# 601_PCIe-USB.net
KiCad netlist of a schematic drawn in Altium Designer
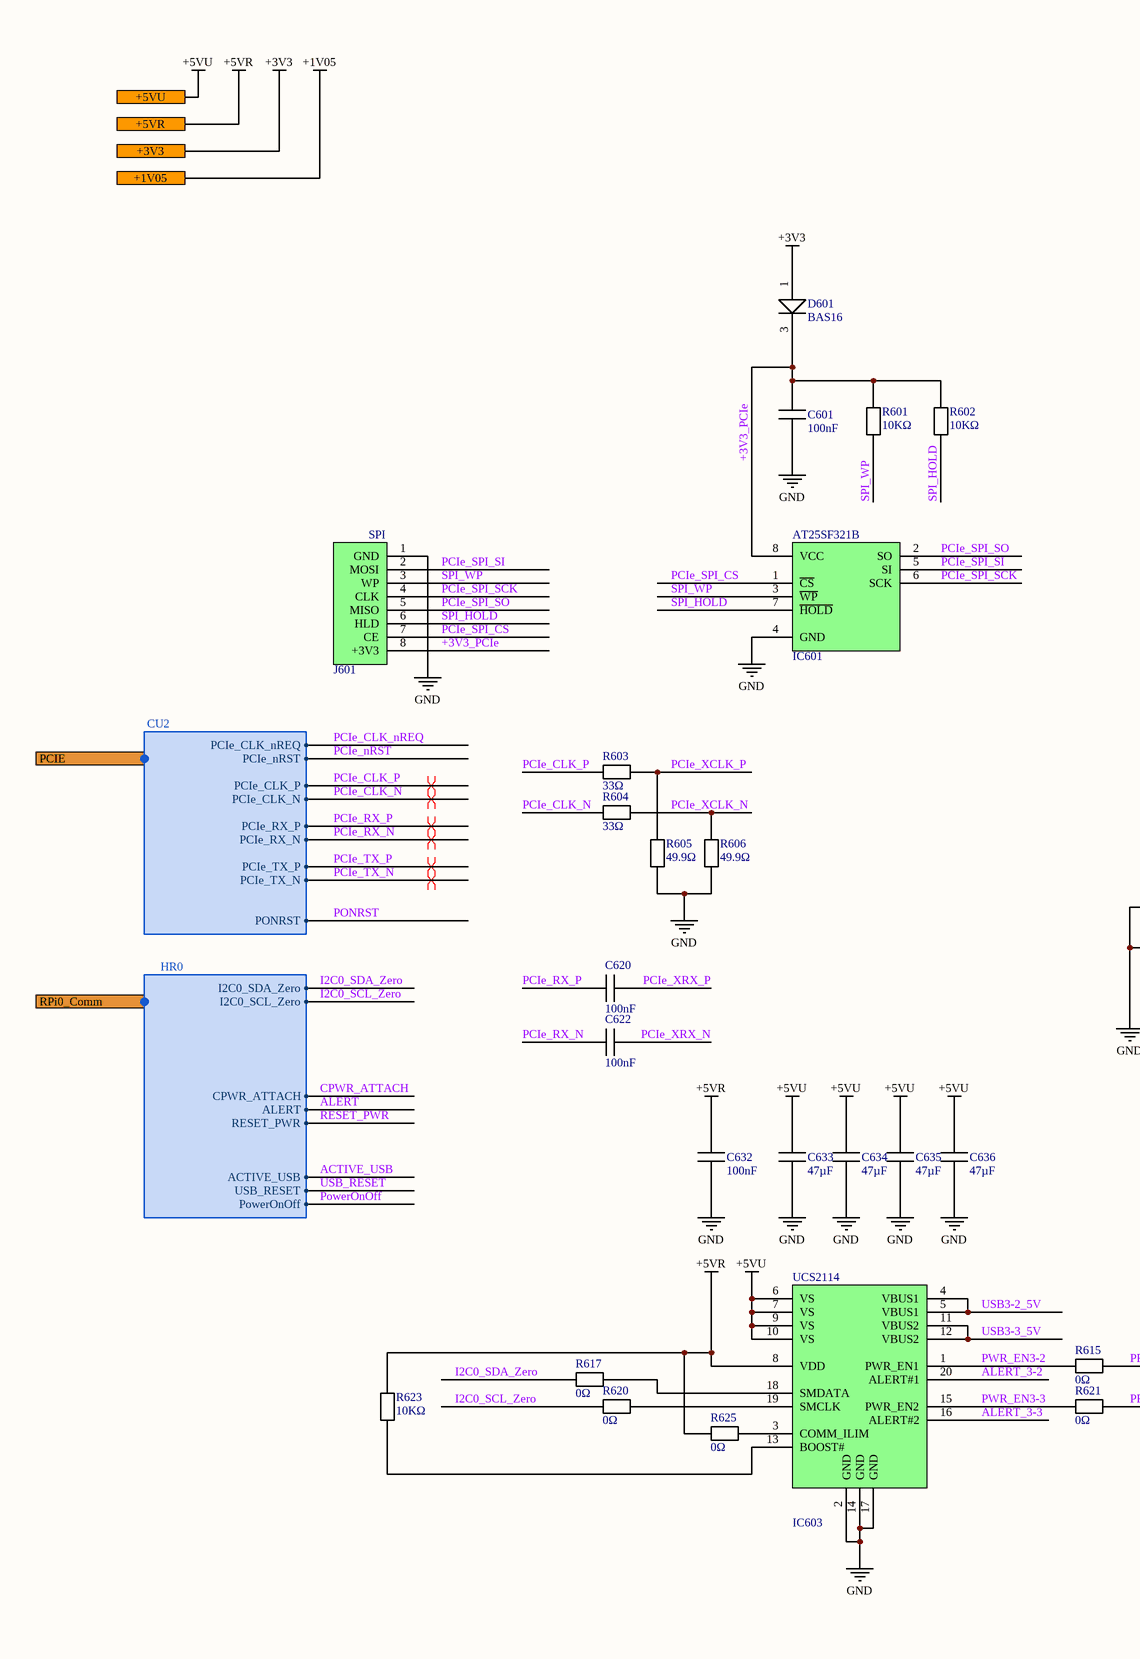
[diagram p0: 601_PCIe-USB.SchDoc, left]
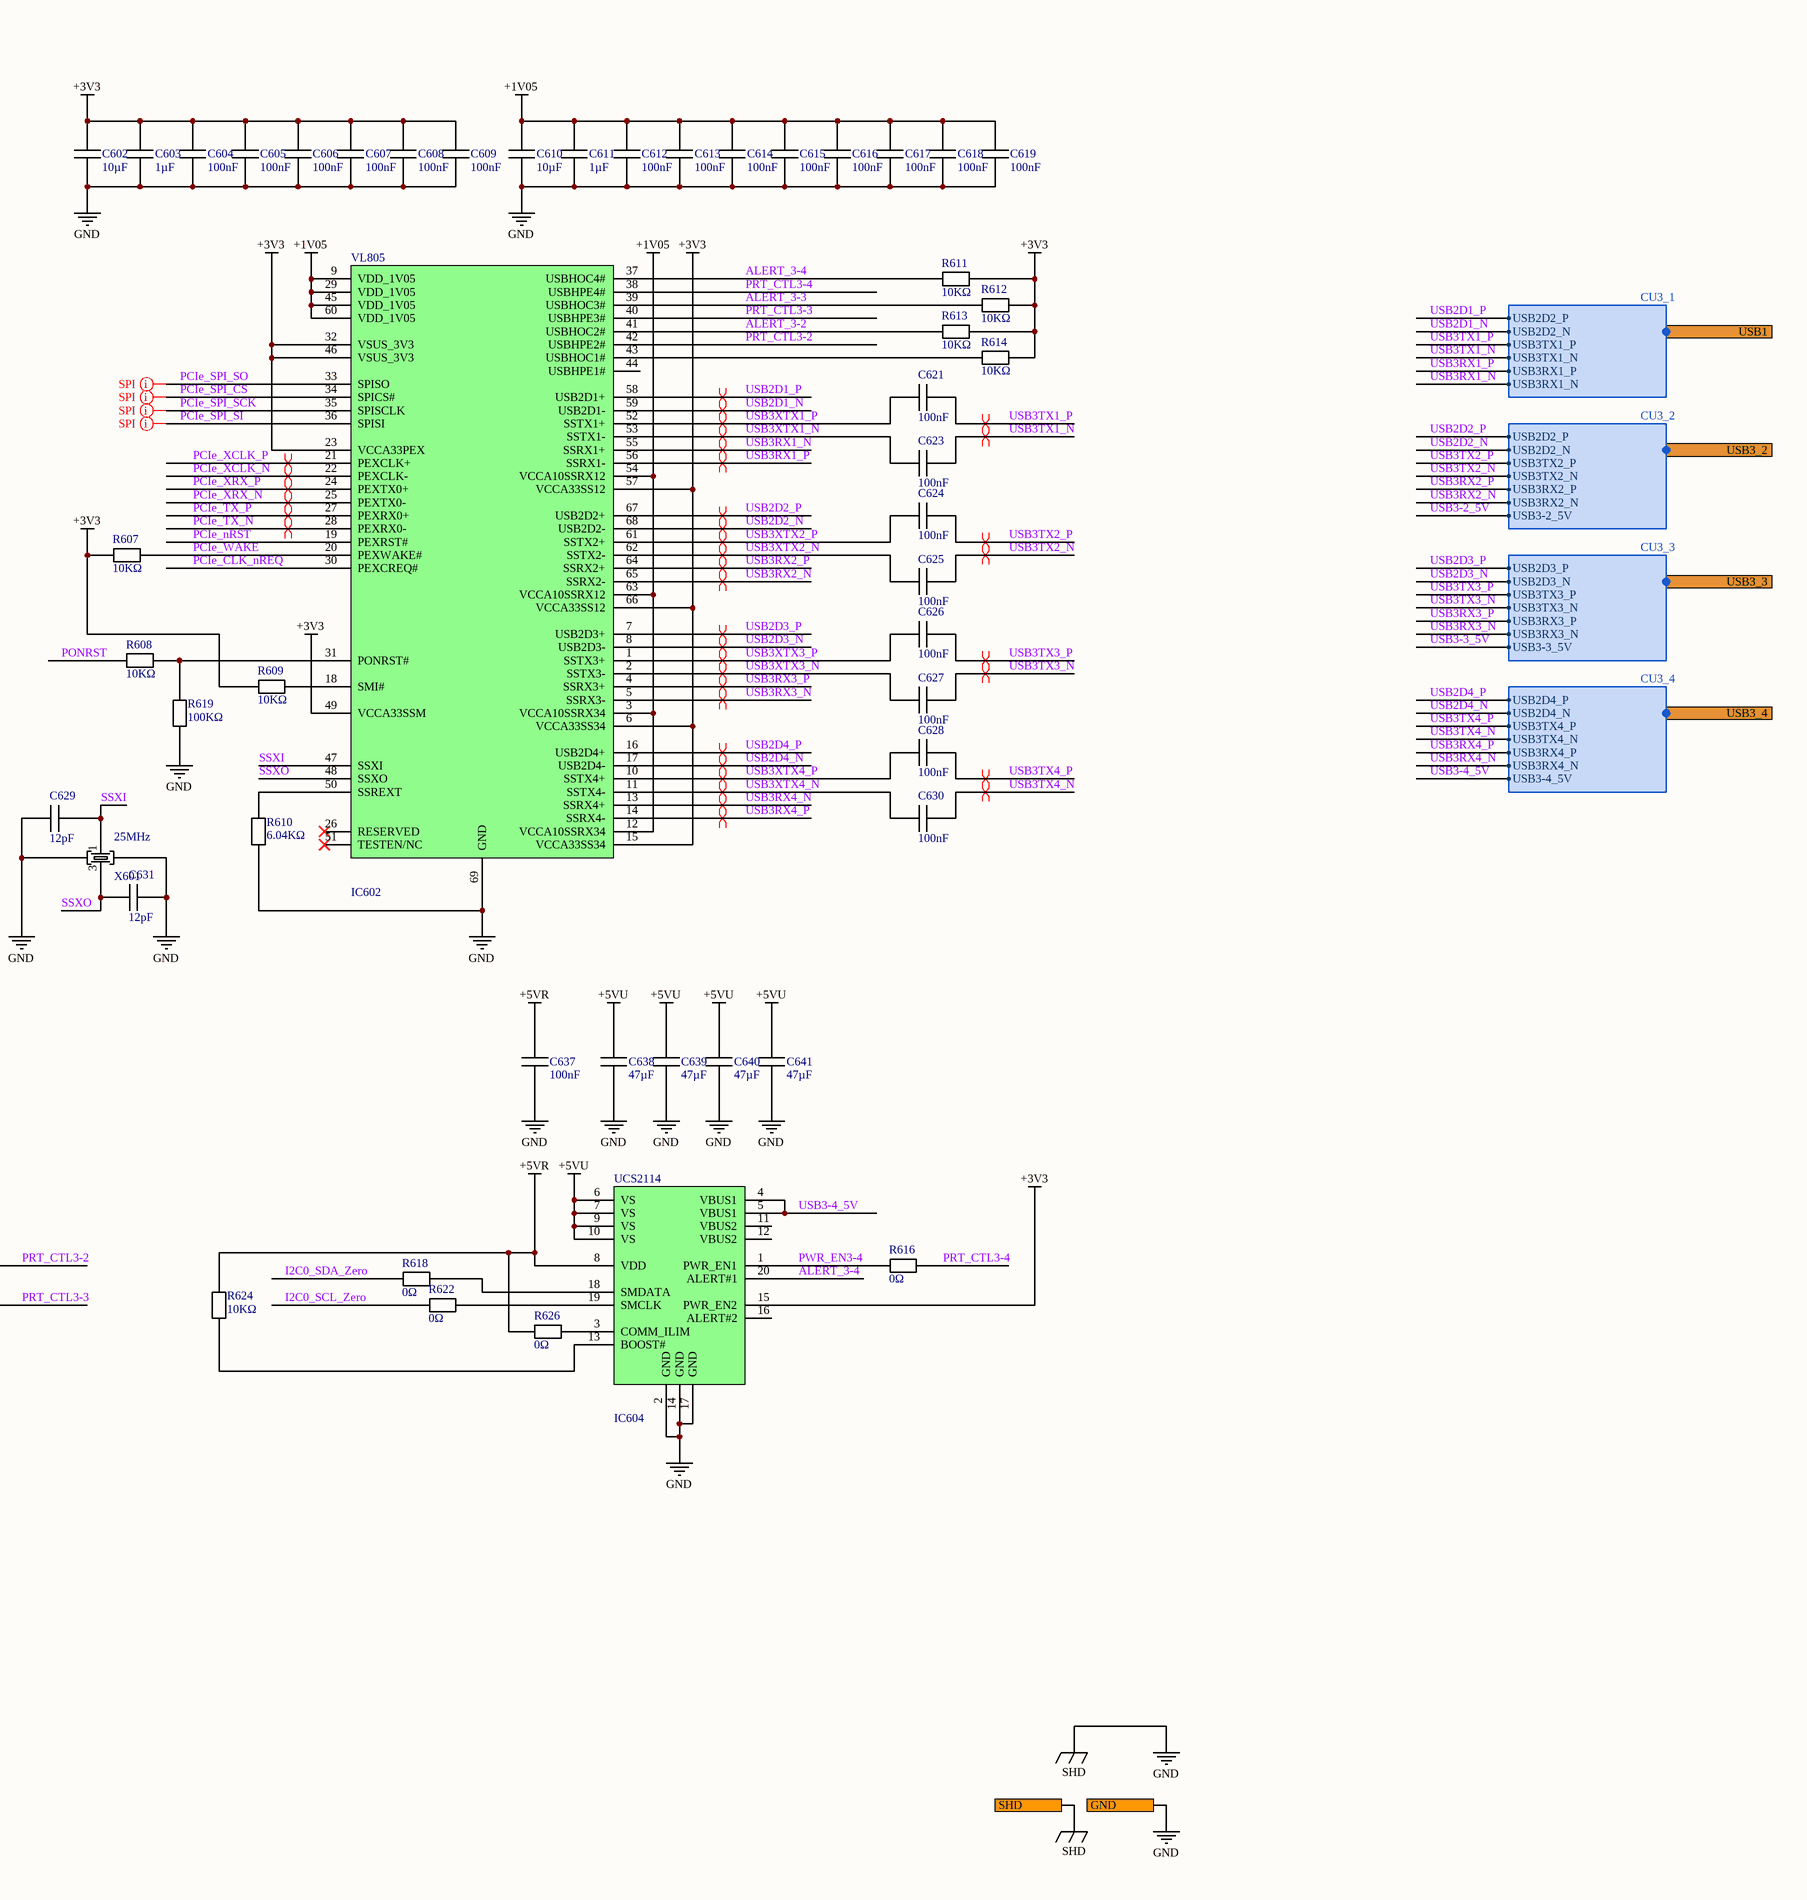
[diagram p1: 601_PCIe-USB.SchDoc, right]

(export (version "E")
  (design (tool "Eeschema 10.0.6"))
  (components
    (comp (ref "C601")
      (value "100nF")
      (footprint "C0402")
      (description "100nF 16V 10% X7R")
      (fields
        (field (name "REFVAL") "100nF")
        (field (name "PART NUMBER") "CA0010")
        (field (name "MANFACTPART") "GCM155R71C104KA55D")
      )
      (libsource (lib "GTS_Database") (part "C"))
    )
    (comp (ref "C602")
      (value "10µF")
      (footprint "C0603")
      (description "10µF 16V 20% X5R")
      (fields
        (field (name "REFVAL") "10µF")
        (field (name "PART NUMBER") "CA0008")
        (field (name "MANFACTPART") "GRM188R61C106MAALD")
      )
      (libsource (lib "GTS_Database") (part "C"))
    )
    (comp (ref "C603")
      (value "1µF")
      (footprint "C0603")
      (description "1µF 16V 10% X5R")
      (fields
        (field (name "REFVAL") "1µF")
        (field (name "PART NUMBER") "CA0003")
        (field (name "MANFACTPART") "C1608X5R1C105K080AA")
      )
      (libsource (lib "GTS_Database") (part "C"))
    )
    (comp (ref "C604")
      (value "100nF")
      (footprint "C0402")
      (description "100nF 16V 10% X7R")
      (fields
        (field (name "REFVAL") "100nF")
        (field (name "PART NUMBER") "CA0010")
        (field (name "MANFACTPART") "GCM155R71C104KA55D")
      )
      (libsource (lib "GTS_Database") (part "C"))
    )
    (comp (ref "C605")
      (value "100nF")
      (footprint "C0402")
      (description "100nF 16V 10% X7R")
      (fields
        (field (name "REFVAL") "100nF")
        (field (name "PART NUMBER") "CA0010")
        (field (name "MANFACTPART") "GCM155R71C104KA55D")
      )
      (libsource (lib "GTS_Database") (part "C"))
    )
    (comp (ref "C606")
      (value "100nF")
      (footprint "C0402")
      (description "100nF 16V 10% X7R")
      (fields
        (field (name "REFVAL") "100nF")
        (field (name "PART NUMBER") "CA0010")
        (field (name "MANFACTPART") "GCM155R71C104KA55D")
      )
      (libsource (lib "GTS_Database") (part "C"))
    )
    (comp (ref "C607")
      (value "100nF")
      (footprint "C0402")
      (description "100nF 16V 10% X7R")
      (fields
        (field (name "REFVAL") "100nF")
        (field (name "PART NUMBER") "CA0010")
        (field (name "MANFACTPART") "GCM155R71C104KA55D")
      )
      (libsource (lib "GTS_Database") (part "C"))
    )
    (comp (ref "C608")
      (value "100nF")
      (footprint "C0402")
      (description "100nF 16V 10% X7R")
      (fields
        (field (name "REFVAL") "100nF")
        (field (name "PART NUMBER") "CA0010")
        (field (name "MANFACTPART") "GCM155R71C104KA55D")
      )
      (libsource (lib "GTS_Database") (part "C"))
    )
    (comp (ref "C609")
      (value "100nF")
      (footprint "C0402")
      (description "100nF 16V 10% X7R")
      (fields
        (field (name "REFVAL") "100nF")
        (field (name "PART NUMBER") "CA0010")
        (field (name "MANFACTPART") "GCM155R71C104KA55D")
      )
      (libsource (lib "GTS_Database") (part "C"))
    )
    (comp (ref "C610")
      (value "10µF")
      (footprint "C0603")
      (description "10µF 16V 20% X5R")
      (fields
        (field (name "REFVAL") "10µF")
        (field (name "PART NUMBER") "CA0008")
        (field (name "MANFACTPART") "GRM188R61C106MAALD")
      )
      (libsource (lib "GTS_Database") (part "C"))
    )
    (comp (ref "C611")
      (value "1µF")
      (footprint "C0603")
      (description "1µF 16V 10% X5R")
      (fields
        (field (name "REFVAL") "1µF")
        (field (name "PART NUMBER") "CA0003")
        (field (name "MANFACTPART") "C1608X5R1C105K080AA")
      )
      (libsource (lib "GTS_Database") (part "C"))
    )
    (comp (ref "C612")
      (value "100nF")
      (footprint "C0402")
      (description "100nF 16V 10% X7R")
      (fields
        (field (name "REFVAL") "100nF")
        (field (name "PART NUMBER") "CA0010")
        (field (name "MANFACTPART") "GCM155R71C104KA55D")
      )
      (libsource (lib "GTS_Database") (part "C"))
    )
    (comp (ref "C613")
      (value "100nF")
      (footprint "C0402")
      (description "100nF 16V 10% X7R")
      (fields
        (field (name "REFVAL") "100nF")
        (field (name "PART NUMBER") "CA0010")
        (field (name "MANFACTPART") "GCM155R71C104KA55D")
      )
      (libsource (lib "GTS_Database") (part "C"))
    )
    (comp (ref "C614")
      (value "100nF")
      (footprint "C0402")
      (description "100nF 16V 10% X7R")
      (fields
        (field (name "REFVAL") "100nF")
        (field (name "PART NUMBER") "CA0010")
        (field (name "MANFACTPART") "GCM155R71C104KA55D")
      )
      (libsource (lib "GTS_Database") (part "C"))
    )
    (comp (ref "C615")
      (value "100nF")
      (footprint "C0402")
      (description "100nF 16V 10% X7R")
      (fields
        (field (name "REFVAL") "100nF")
        (field (name "PART NUMBER") "CA0010")
        (field (name "MANFACTPART") "GCM155R71C104KA55D")
      )
      (libsource (lib "GTS_Database") (part "C"))
    )
    (comp (ref "C616")
      (value "100nF")
      (footprint "C0402")
      (description "100nF 16V 10% X7R")
      (fields
        (field (name "REFVAL") "100nF")
        (field (name "PART NUMBER") "CA0010")
        (field (name "MANFACTPART") "GCM155R71C104KA55D")
      )
      (libsource (lib "GTS_Database") (part "C"))
    )
    (comp (ref "C617")
      (value "100nF")
      (footprint "C0402")
      (description "100nF 16V 10% X7R")
      (fields
        (field (name "REFVAL") "100nF")
        (field (name "PART NUMBER") "CA0010")
        (field (name "MANFACTPART") "GCM155R71C104KA55D")
      )
      (libsource (lib "GTS_Database") (part "C"))
    )
    (comp (ref "C618")
      (value "100nF")
      (footprint "C0402")
      (description "100nF 16V 10% X7R")
      (fields
        (field (name "REFVAL") "100nF")
        (field (name "PART NUMBER") "CA0010")
        (field (name "MANFACTPART") "GCM155R71C104KA55D")
      )
      (libsource (lib "GTS_Database") (part "C"))
    )
    (comp (ref "C619")
      (value "100nF")
      (footprint "C0402")
      (description "100nF 16V 10% X7R")
      (fields
        (field (name "REFVAL") "100nF")
        (field (name "PART NUMBER") "CA0010")
        (field (name "MANFACTPART") "GCM155R71C104KA55D")
      )
      (libsource (lib "GTS_Database") (part "C"))
    )
    (comp (ref "C620")
      (value "100nF")
      (footprint "C0402")
      (description "100nF 16V 10% X7R")
      (fields
        (field (name "REFVAL") "100nF")
        (field (name "PART NUMBER") "CA0010")
        (field (name "MANFACTPART") "GCM155R71C104KA55D")
      )
      (libsource (lib "GTS_Database") (part "C"))
    )
    (comp (ref "C621")
      (value "100nF")
      (footprint "C0402")
      (description "100nF 16V 10% X7R")
      (fields
        (field (name "REFVAL") "100nF")
        (field (name "PART NUMBER") "CA0010")
        (field (name "MANFACTPART") "GCM155R71C104KA55D")
      )
      (libsource (lib "GTS_Database") (part "C"))
    )
    (comp (ref "C622")
      (value "100nF")
      (footprint "C0402")
      (description "100nF 16V 10% X7R")
      (fields
        (field (name "REFVAL") "100nF")
        (field (name "PART NUMBER") "CA0010")
        (field (name "MANFACTPART") "GCM155R71C104KA55D")
      )
      (libsource (lib "GTS_Database") (part "C"))
    )
    (comp (ref "C623")
      (value "100nF")
      (footprint "C0402")
      (description "100nF 16V 10% X7R")
      (fields
        (field (name "REFVAL") "100nF")
        (field (name "PART NUMBER") "CA0010")
        (field (name "MANFACTPART") "GCM155R71C104KA55D")
      )
      (libsource (lib "GTS_Database") (part "C"))
    )
    (comp (ref "C624")
      (value "100nF")
      (footprint "C0402")
      (description "100nF 16V 10% X7R")
      (fields
        (field (name "REFVAL") "100nF")
        (field (name "PART NUMBER") "CA0010")
        (field (name "MANFACTPART") "GCM155R71C104KA55D")
      )
      (libsource (lib "GTS_Database") (part "C"))
    )
    (comp (ref "C625")
      (value "100nF")
      (footprint "C0402")
      (description "100nF 16V 10% X7R")
      (fields
        (field (name "REFVAL") "100nF")
        (field (name "PART NUMBER") "CA0010")
        (field (name "MANFACTPART") "GCM155R71C104KA55D")
      )
      (libsource (lib "GTS_Database") (part "C"))
    )
    (comp (ref "C626")
      (value "100nF")
      (footprint "C0402")
      (description "100nF 16V 10% X7R")
      (fields
        (field (name "REFVAL") "100nF")
        (field (name "PART NUMBER") "CA0010")
        (field (name "MANFACTPART") "GCM155R71C104KA55D")
      )
      (libsource (lib "GTS_Database") (part "C"))
    )
    (comp (ref "C627")
      (value "100nF")
      (footprint "C0402")
      (description "100nF 16V 10% X7R")
      (fields
        (field (name "REFVAL") "100nF")
        (field (name "PART NUMBER") "CA0010")
        (field (name "MANFACTPART") "GCM155R71C104KA55D")
      )
      (libsource (lib "GTS_Database") (part "C"))
    )
    (comp (ref "C628")
      (value "100nF")
      (footprint "C0402")
      (description "100nF 16V 10% X7R")
      (fields
        (field (name "REFVAL") "100nF")
        (field (name "PART NUMBER") "CA0010")
        (field (name "MANFACTPART") "GCM155R71C104KA55D")
      )
      (libsource (lib "GTS_Database") (part "C"))
    )
    (comp (ref "C629")
      (value "12pF")
      (footprint "C0402")
      (description "12pF 16V 1% C0G")
      (fields
        (field (name "REFVAL") "12pF")
        (field (name "PART NUMBER") "CA0059")
        (field (name "MANFACTPART") "VJ0402A120FXJCW1BC")
      )
      (libsource (lib "GTS_Database") (part "C"))
    )
    (comp (ref "C630")
      (value "100nF")
      (footprint "C0402")
      (description "100nF 16V 10% X7R")
      (fields
        (field (name "REFVAL") "100nF")
        (field (name "PART NUMBER") "CA0010")
        (field (name "MANFACTPART") "GCM155R71C104KA55D")
      )
      (libsource (lib "GTS_Database") (part "C"))
    )
    (comp (ref "C631")
      (value "12pF")
      (footprint "C0402")
      (description "12pF 16V 1% C0G")
      (fields
        (field (name "REFVAL") "12pF")
        (field (name "PART NUMBER") "CA0059")
        (field (name "MANFACTPART") "VJ0402A120FXJCW1BC")
      )
      (libsource (lib "GTS_Database") (part "C"))
    )
    (comp (ref "C632")
      (value "100nF")
      (footprint "C0402")
      (description "100nF 16V 10% X7R")
      (fields
        (field (name "REFVAL") "100nF")
        (field (name "PART NUMBER") "CA0010")
        (field (name "MANFACTPART") "GCM155R71C104KA55D")
      )
      (libsource (lib "GTS_Database") (part "C"))
    )
    (comp (ref "C633")
      (value "47µF")
      (footprint "C1210")
      (description "47µF 16V 20% X5R")
      (fields
        (field (name "REFVAL") "47µF")
        (field (name "PART NUMBER") "CA0007")
        (field (name "MANFACTPART") "EMK325ABJ476MM8P")
      )
      (libsource (lib "GTS_Database") (part "C"))
    )
    (comp (ref "C634")
      (value "47µF")
      (footprint "C1210")
      (description "47µF 16V 20% X5R")
      (fields
        (field (name "REFVAL") "47µF")
        (field (name "PART NUMBER") "CA0007")
        (field (name "MANFACTPART") "EMK325ABJ476MM8P")
      )
      (libsource (lib "GTS_Database") (part "C"))
    )
    (comp (ref "C635")
      (value "47µF")
      (footprint "C1210")
      (description "47µF 16V 20% X5R")
      (fields
        (field (name "REFVAL") "47µF")
        (field (name "PART NUMBER") "CA0007")
        (field (name "MANFACTPART") "EMK325ABJ476MM8P")
      )
      (libsource (lib "GTS_Database") (part "C"))
    )
    (comp (ref "C636")
      (value "47µF")
      (footprint "C1210")
      (description "47µF 16V 20% X5R")
      (fields
        (field (name "REFVAL") "47µF")
        (field (name "PART NUMBER") "CA0007")
        (field (name "MANFACTPART") "EMK325ABJ476MM8P")
      )
      (libsource (lib "GTS_Database") (part "C"))
    )
    (comp (ref "C637")
      (value "100nF")
      (footprint "C0402")
      (description "100nF 16V 10% X7R")
      (fields
        (field (name "REFVAL") "100nF")
        (field (name "PART NUMBER") "CA0010")
        (field (name "MANFACTPART") "GCM155R71C104KA55D")
      )
      (libsource (lib "GTS_Database") (part "C"))
    )
    (comp (ref "C638")
      (value "47µF")
      (footprint "C1210")
      (description "47µF 16V 20% X5R")
      (fields
        (field (name "REFVAL") "47µF")
        (field (name "PART NUMBER") "CA0007")
        (field (name "MANFACTPART") "EMK325ABJ476MM8P")
      )
      (libsource (lib "GTS_Database") (part "C"))
    )
    (comp (ref "C639")
      (value "47µF")
      (footprint "C1210")
      (description "47µF 16V 20% X5R")
      (fields
        (field (name "REFVAL") "47µF")
        (field (name "PART NUMBER") "CA0007")
        (field (name "MANFACTPART") "EMK325ABJ476MM8P")
      )
      (libsource (lib "GTS_Database") (part "C"))
    )
    (comp (ref "C640")
      (value "47µF")
      (footprint "C1210")
      (description "47µF 16V 20% X5R")
      (fields
        (field (name "REFVAL") "47µF")
        (field (name "PART NUMBER") "CA0007")
        (field (name "MANFACTPART") "EMK325ABJ476MM8P")
      )
      (libsource (lib "GTS_Database") (part "C"))
    )
    (comp (ref "C641")
      (value "47µF")
      (footprint "C1210")
      (description "47µF 16V 20% X5R")
      (fields
        (field (name "REFVAL") "47µF")
        (field (name "PART NUMBER") "CA0007")
        (field (name "MANFACTPART") "EMK325ABJ476MM8P")
      )
      (libsource (lib "GTS_Database") (part "C"))
    )
    (comp (ref "D601")
      (value "BAS16")
      (footprint "SOT-23")
      (description "Diodes - General Purpose, Power, Switching 100Vll Signal Switching Diodes 2A")
      (fields
        (field (name "REFVAL") "BAS16")
        (field (name "PART NUMBER") "DI0010")
        (field (name "MANFACTPART") "BAS16_R1_00001")
      )
      (libsource (lib "GTS_Database") (part "Ddefault_3P"))
    )
    (comp (ref "IC601")
      (value "AT25SF321B")
      (footprint "SO-8")
      (description "32-Mbit SPI Serial Flash Memory with Dual-I/O and Quad-I/O Support")
      (fields
        (field (name "REFVAL") "AT25SF321B")
        (field (name "PART NUMBER") "IC0053")
        (field (name "MANFACTPART") "AT25SF321B-SSHB-T")
      )
      (libsource (lib "GTS_Database") (part "AT25SF321B"))
    )
    (comp (ref "IC602")
      (value "VL805")
      (footprint "QFN-68G_8X8")
      (description "VL805 4-Port USB 3.0 Host Controller")
      (fields
        (field (name "REFVAL") "VL805")
        (field (name "PART NUMBER") "IC0046")
        (field (name "MANFACTPART") "VL805-Q6")
      )
      (libsource (lib "GTS_Database") (part "VL805"))
    )
    (comp (ref "IC603")
      (value "UCS2114")
      (footprint "VQFN-20_3X3")
      (description "Dual USB Power Switch with Integrated Current Sensor")
      (fields (field (name "REFVAL") "UCS2114") (field (name "PART NUMBER") "IC0056"))
      (libsource (lib "GTS_Database") (part "UCS2114"))
    )
    (comp (ref "IC604")
      (value "UCS2114")
      (footprint "VQFN-20_3X3")
      (description "Dual USB Power Switch with Integrated Current Sensor")
      (fields (field (name "REFVAL") "UCS2114") (field (name "PART NUMBER") "IC0056"))
      (libsource (lib "GTS_Database") (part "UCS2114"))
    )
    (comp (ref "J601")
      (value "SPI")
      (footprint "SPI_PROG_TYPE1")
      (description "SPI Programming connection")
      (fields (field (name "REFVAL") "SPI") (field (name "PART NUMBER") "ME0028"))
      (libsource (lib "GTS_Database") (part "SPI_PROG_TYPE1"))
    )
    (comp (ref "R601")
      (value "10KΩ")
      (footprint "R0402")
      (description "10KΩ 1% 62.5mW")
      (fields
        (field (name "REFVAL") "10KΩ")
        (field (name "PART NUMBER") "RS0011")
        (field (name "MANFACTPART") "WR04X1002FTL")
      )
      (libsource (lib "GTS_Database") (part "R"))
    )
    (comp (ref "R602")
      (value "10KΩ")
      (footprint "R0402")
      (description "10KΩ 1% 62.5mW")
      (fields
        (field (name "REFVAL") "10KΩ")
        (field (name "PART NUMBER") "RS0011")
        (field (name "MANFACTPART") "WR04X1002FTL")
      )
      (libsource (lib "GTS_Database") (part "R"))
    )
    (comp (ref "R603")
      (value "33Ω")
      (footprint "R0201")
      (description "33Ω 5% 50mW 200PPM")
      (fields
        (field (name "REFVAL") "33Ω")
        (field (name "PART NUMBER") "RS0067")
        (field (name "MANFACTPART") "0201WMJ0330TEE")
      )
      (libsource (lib "GTS_Database") (part "R"))
    )
    (comp (ref "R604")
      (value "33Ω")
      (footprint "R0201")
      (description "33Ω 5% 50mW 200PPM")
      (fields
        (field (name "REFVAL") "33Ω")
        (field (name "PART NUMBER") "RS0067")
        (field (name "MANFACTPART") "0201WMJ0330TEE")
      )
      (libsource (lib "GTS_Database") (part "R"))
    )
    (comp (ref "R605")
      (value "49.9Ω")
      (footprint "R0201")
      (description "49.9Ω 1% 50mW 200PPM")
      (fields
        (field (name "REFVAL") "49.9Ω")
        (field (name "PART NUMBER") "RS0069")
        (field (name "MANFACTPART") "0201WMF499JTEE")
      )
      (libsource (lib "GTS_Database") (part "R"))
    )
    (comp (ref "R606")
      (value "49.9Ω")
      (footprint "R0201")
      (description "49.9Ω 1% 50mW 200PPM")
      (fields
        (field (name "REFVAL") "49.9Ω")
        (field (name "PART NUMBER") "RS0069")
        (field (name "MANFACTPART") "0201WMF499JTEE")
      )
      (libsource (lib "GTS_Database") (part "R"))
    )
    (comp (ref "R607")
      (value "10KΩ")
      (footprint "R0402")
      (description "10KΩ 1% 62.5mW")
      (fields
        (field (name "REFVAL") "10KΩ")
        (field (name "PART NUMBER") "RS0011")
        (field (name "MANFACTPART") "WR04X1002FTL")
      )
      (libsource (lib "GTS_Database") (part "R"))
    )
    (comp (ref "R608")
      (value "10KΩ")
      (footprint "R0402")
      (description "10KΩ 1% 62.5mW")
      (fields
        (field (name "REFVAL") "10KΩ")
        (field (name "PART NUMBER") "RS0011")
        (field (name "MANFACTPART") "WR04X1002FTL")
      )
      (libsource (lib "GTS_Database") (part "R"))
    )
    (comp (ref "R609")
      (value "10KΩ")
      (footprint "R0402")
      (description "10KΩ 1% 62.5mW")
      (fields
        (field (name "REFVAL") "10KΩ")
        (field (name "PART NUMBER") "RS0011")
        (field (name "MANFACTPART") "WR04X1002FTL")
      )
      (libsource (lib "GTS_Database") (part "R"))
    )
    (comp (ref "R610")
      (value "6.04KΩ")
      (footprint "R0402")
      (description "6.04KΩ 1% 62.5mW")
      (fields
        (field (name "REFVAL") "6.04KΩ")
        (field (name "PART NUMBER") "RS0017")
        (field (name "MANFACTPART") "RC0402FR-076K04L")
      )
      (libsource (lib "GTS_Database") (part "R"))
    )
    (comp (ref "R611")
      (value "10KΩ")
      (footprint "R0402")
      (description "10KΩ 1% 62.5mW")
      (fields
        (field (name "REFVAL") "10KΩ")
        (field (name "PART NUMBER") "RS0011")
        (field (name "MANFACTPART") "WR04X1002FTL")
      )
      (libsource (lib "GTS_Database") (part "R"))
    )
    (comp (ref "R612")
      (value "10KΩ")
      (footprint "R0402")
      (description "10KΩ 1% 62.5mW")
      (fields
        (field (name "REFVAL") "10KΩ")
        (field (name "PART NUMBER") "RS0011")
        (field (name "MANFACTPART") "WR04X1002FTL")
      )
      (libsource (lib "GTS_Database") (part "R"))
    )
    (comp (ref "R613")
      (value "10KΩ")
      (footprint "R0402")
      (description "10KΩ 1% 62.5mW")
      (fields
        (field (name "REFVAL") "10KΩ")
        (field (name "PART NUMBER") "RS0011")
        (field (name "MANFACTPART") "WR04X1002FTL")
      )
      (libsource (lib "GTS_Database") (part "R"))
    )
    (comp (ref "R614")
      (value "10KΩ")
      (footprint "R0402")
      (description "10KΩ 1% 62.5mW")
      (fields
        (field (name "REFVAL") "10KΩ")
        (field (name "PART NUMBER") "RS0011")
        (field (name "MANFACTPART") "WR04X1002FTL")
      )
      (libsource (lib "GTS_Database") (part "R"))
    )
    (comp (ref "R615")
      (value "0Ω")
      (footprint "R0402")
      (description "0Ω 62.5mW")
      (fields
        (field (name "REFVAL") "0Ω")
        (field (name "PART NUMBER") "RS0074")
        (field (name "MANFACTPART") "0402WGJ0000TCE")
      )
      (libsource (lib "GTS_Database") (part "R"))
    )
    (comp (ref "R616")
      (value "0Ω")
      (footprint "R0402")
      (description "0Ω 62.5mW")
      (fields
        (field (name "REFVAL") "0Ω")
        (field (name "PART NUMBER") "RS0074")
        (field (name "MANFACTPART") "0402WGJ0000TCE")
      )
      (libsource (lib "GTS_Database") (part "R"))
    )
    (comp (ref "R617")
      (value "0Ω")
      (footprint "R0402")
      (description "0Ω 62.5mW")
      (fields
        (field (name "REFVAL") "0Ω")
        (field (name "PART NUMBER") "RS0074")
        (field (name "MANFACTPART") "0402WGJ0000TCE")
      )
      (libsource (lib "GTS_Database") (part "R"))
    )
    (comp (ref "R618")
      (value "0Ω")
      (footprint "R0402")
      (description "0Ω 62.5mW")
      (fields
        (field (name "REFVAL") "0Ω")
        (field (name "PART NUMBER") "RS0074")
        (field (name "MANFACTPART") "0402WGJ0000TCE")
      )
      (libsource (lib "GTS_Database") (part "R"))
    )
    (comp (ref "R619")
      (value "100KΩ")
      (footprint "R0402")
      (description "100KΩ 1% 62.5mW 100PPM")
      (fields
        (field (name "REFVAL") "100KΩ")
        (field (name "PART NUMBER") "RS0036")
        (field (name "MANFACTPART") "AC0402FR-13100KL")
      )
      (libsource (lib "GTS_Database") (part "R"))
    )
    (comp (ref "R620")
      (value "0Ω")
      (footprint "R0402")
      (description "0Ω 62.5mW")
      (fields
        (field (name "REFVAL") "0Ω")
        (field (name "PART NUMBER") "RS0074")
        (field (name "MANFACTPART") "0402WGJ0000TCE")
      )
      (libsource (lib "GTS_Database") (part "R"))
    )
    (comp (ref "R621")
      (value "0Ω")
      (footprint "R0402")
      (description "0Ω 62.5mW")
      (fields
        (field (name "REFVAL") "0Ω")
        (field (name "PART NUMBER") "RS0074")
        (field (name "MANFACTPART") "0402WGJ0000TCE")
      )
      (libsource (lib "GTS_Database") (part "R"))
    )
    (comp (ref "R622")
      (value "0Ω")
      (footprint "R0402")
      (description "0Ω 62.5mW")
      (fields
        (field (name "REFVAL") "0Ω")
        (field (name "PART NUMBER") "RS0074")
        (field (name "MANFACTPART") "0402WGJ0000TCE")
      )
      (libsource (lib "GTS_Database") (part "R"))
    )
    (comp (ref "R623")
      (value "10KΩ")
      (footprint "R0402")
      (description "10KΩ 1% 62.5mW")
      (fields
        (field (name "REFVAL") "10KΩ")
        (field (name "PART NUMBER") "RS0011")
        (field (name "MANFACTPART") "WR04X1002FTL")
      )
      (libsource (lib "GTS_Database") (part "R"))
    )
    (comp (ref "R624")
      (value "10KΩ")
      (footprint "R0402")
      (description "10KΩ 1% 62.5mW")
      (fields
        (field (name "REFVAL") "10KΩ")
        (field (name "PART NUMBER") "RS0011")
        (field (name "MANFACTPART") "WR04X1002FTL")
      )
      (libsource (lib "GTS_Database") (part "R"))
    )
    (comp (ref "R625")
      (value "0Ω")
      (footprint "R0402")
      (description "0Ω 62.5mW")
      (fields
        (field (name "REFVAL") "0Ω")
        (field (name "PART NUMBER") "RS0074")
        (field (name "MANFACTPART") "0402WGJ0000TCE")
      )
      (libsource (lib "GTS_Database") (part "R"))
    )
    (comp (ref "R626")
      (value "0Ω")
      (footprint "R0402")
      (description "0Ω 62.5mW")
      (fields
        (field (name "REFVAL") "0Ω")
        (field (name "PART NUMBER") "RS0074")
        (field (name "MANFACTPART") "0402WGJ0000TCE")
      )
      (libsource (lib "GTS_Database") (part "R"))
    )
    (comp (ref "X601")
      (value "25MHz")
      (footprint "403W")
      (description "25MHz 8pF 20PPM")
      (fields
        (field (name "REFVAL") "25MHz")
        (field (name "PART NUMBER") "CR0003")
        (field (name "MANFACTPART") "403WF25012IK")
      )
      (libsource (lib "GTS_Database") (part "Crystal_1_3"))
    )
  )
  (nets
    (net (code "7") (name "+1V05") (class "Default")
      (node (ref "C610") (pin "1") (pinfunction "1_1") (pintype "passive"))
      (node (ref "C611") (pin "1") (pinfunction "1_1") (pintype "passive"))
      (node (ref "C612") (pin "1") (pinfunction "1_1") (pintype "passive"))
      (node (ref "C613") (pin "1") (pinfunction "1_1") (pintype "passive"))
      (node (ref "C614") (pin "1") (pinfunction "1_1") (pintype "passive"))
      (node (ref "C615") (pin "1") (pinfunction "1_1") (pintype "passive"))
      (node (ref "C616") (pin "1") (pinfunction "1_1") (pintype "passive"))
      (node (ref "C617") (pin "1") (pinfunction "1_1") (pintype "passive"))
      (node (ref "C618") (pin "1") (pinfunction "1_1") (pintype "passive"))
      (node (ref "C619") (pin "1") (pinfunction "1_1") (pintype "passive"))
      (node (ref "IC602") (pin "12") (pinfunction "VCCA10SSRX34_12") (pintype "passive"))
      (node (ref "IC602") (pin "29") (pinfunction "VDD_1V05_29") (pintype "passive"))
      (node (ref "IC602") (pin "3") (pinfunction "VCCA10SSRX34_3") (pintype "passive"))
      (node (ref "IC602") (pin "45") (pinfunction "VDD_1V05_45") (pintype "passive"))
      (node (ref "IC602") (pin "54") (pinfunction "VCCA10SSRX12_54") (pintype "passive"))
      (node (ref "IC602") (pin "60") (pinfunction "VDD_1V05_60") (pintype "passive"))
      (node (ref "IC602") (pin "63") (pinfunction "VCCA10SSRX12_63") (pintype "passive"))
      (node (ref "IC602") (pin "9") (pinfunction "VDD_1V05_9") (pintype "passive"))
    )
    (net (code "8") (name "+3V3") (class "Default")
      (node (ref "C602") (pin "1") (pinfunction "1_1") (pintype "passive"))
      (node (ref "C603") (pin "1") (pinfunction "1_1") (pintype "passive"))
      (node (ref "C604") (pin "1") (pinfunction "1_1") (pintype "passive"))
      (node (ref "C605") (pin "1") (pinfunction "1_1") (pintype "passive"))
      (node (ref "C606") (pin "1") (pinfunction "1_1") (pintype "passive"))
      (node (ref "C607") (pin "1") (pinfunction "1_1") (pintype "passive"))
      (node (ref "C608") (pin "1") (pinfunction "1_1") (pintype "passive"))
      (node (ref "C609") (pin "1") (pinfunction "1_1") (pintype "passive"))
      (node (ref "D601") (pin "1") (pinfunction "A_1") (pintype "passive"))
      (node (ref "IC602") (pin "15") (pinfunction "VCCA33SS34_15") (pintype "passive"))
      (node (ref "IC602") (pin "23") (pinfunction "VCCA33PEX_23") (pintype "passive"))
      (node (ref "IC602") (pin "32") (pinfunction "VSUS_3V3_32") (pintype "passive"))
      (node (ref "IC602") (pin "46") (pinfunction "VSUS_3V3_46") (pintype "passive"))
      (node (ref "IC602") (pin "49") (pinfunction "VCCA33SSM_49") (pintype "passive"))
      (node (ref "IC602") (pin "57") (pinfunction "VCCA33SS12_57") (pintype "passive"))
      (node (ref "IC602") (pin "6") (pinfunction "VCCA33SS34_6") (pintype "passive"))
      (node (ref "IC602") (pin "66") (pinfunction "VCCA33SS12_66") (pintype "passive"))
      (node (ref "IC604") (pin "15") (pinfunction "PWR_EN2_15") (pintype "passive"))
      (node (ref "R607") (pin "2") (pinfunction "2_2") (pintype "passive"))
      (node (ref "R609") (pin "1") (pinfunction "1_1") (pintype "passive"))
      (node (ref "R611") (pin "1") (pinfunction "1_1") (pintype "passive"))
      (node (ref "R612") (pin "1") (pinfunction "1_1") (pintype "passive"))
      (node (ref "R613") (pin "1") (pinfunction "1_1") (pintype "passive"))
      (node (ref "R614") (pin "1") (pinfunction "1_1") (pintype "passive"))
    )
    (net (code "9") (name "+5VR") (class "Default")
      (node (ref "C632") (pin "1") (pinfunction "1_1") (pintype "passive"))
      (node (ref "C637") (pin "1") (pinfunction "1_1") (pintype "passive"))
      (node (ref "IC603") (pin "8") (pinfunction "VDD_8") (pintype "passive"))
      (node (ref "IC604") (pin "8") (pinfunction "VDD_8") (pintype "passive"))
      (node (ref "R623") (pin "2") (pinfunction "2_2") (pintype "passive"))
      (node (ref "R624") (pin "2") (pinfunction "2_2") (pintype "passive"))
      (node (ref "R625") (pin "1") (pinfunction "1_1") (pintype "passive"))
      (node (ref "R626") (pin "1") (pinfunction "1_1") (pintype "passive"))
    )
    (net (code "10") (name "+5VU") (class "Default")
      (node (ref "C633") (pin "1") (pinfunction "1_1") (pintype "passive"))
      (node (ref "C634") (pin "1") (pinfunction "1_1") (pintype "passive"))
      (node (ref "C635") (pin "1") (pinfunction "1_1") (pintype "passive"))
      (node (ref "C636") (pin "1") (pinfunction "1_1") (pintype "passive"))
      (node (ref "C638") (pin "1") (pinfunction "1_1") (pintype "passive"))
      (node (ref "C639") (pin "1") (pinfunction "1_1") (pintype "passive"))
      (node (ref "C640") (pin "1") (pinfunction "1_1") (pintype "passive"))
      (node (ref "C641") (pin "1") (pinfunction "1_1") (pintype "passive"))
      (node (ref "IC603") (pin "10") (pinfunction "VS_10") (pintype "passive"))
      (node (ref "IC603") (pin "6") (pinfunction "VS_6") (pintype "passive"))
      (node (ref "IC603") (pin "7") (pinfunction "VS_7") (pintype "passive"))
      (node (ref "IC603") (pin "9") (pinfunction "VS_9") (pintype "passive"))
      (node (ref "IC604") (pin "10") (pinfunction "VS_10") (pintype "passive"))
      (node (ref "IC604") (pin "6") (pinfunction "VS_6") (pintype "passive"))
      (node (ref "IC604") (pin "7") (pinfunction "VS_7") (pintype "passive"))
      (node (ref "IC604") (pin "9") (pinfunction "VS_9") (pintype "passive"))
    )
    (net (code "11") (name "/+3V3_PCIe") (class "Default")
      (node (ref "C601") (pin "1") (pinfunction "1_1") (pintype "passive"))
      (node (ref "D601") (pin "3") (pinfunction "K_3") (pintype "passive"))
      (node (ref "IC601") (pin "8") (pinfunction "VCC_8") (pintype "passive"))
      (node (ref "J601") (pin "8") (pinfunction "+3V3_8") (pintype "passive"))
      (node (ref "R601") (pin "1") (pinfunction "1_1") (pintype "passive"))
      (node (ref "R602") (pin "1") (pinfunction "1_1") (pintype "passive"))
    )
    (net (code "14") (name "/ALERT_3-2") (class "Default")
      (node (ref "IC602") (pin "41") (pinfunction "USBHOC2#_41") (pintype "passive"))
      (node (ref "IC603") (pin "20") (pinfunction "ALERT#1_20") (pintype "passive"))
      (node (ref "R613") (pin "2") (pinfunction "2_2") (pintype "passive"))
    )
    (net (code "15") (name "/ALERT_3-3") (class "Default")
      (node (ref "IC602") (pin "39") (pinfunction "USBHOC3#_39") (pintype "passive"))
      (node (ref "IC603") (pin "16") (pinfunction "ALERT#2_16") (pintype "passive"))
      (node (ref "R612") (pin "2") (pinfunction "2_2") (pintype "passive"))
    )
    (net (code "16") (name "/ALERT_3-4") (class "Default")
      (node (ref "IC602") (pin "37") (pinfunction "USBHOC4#_37") (pintype "passive"))
      (node (ref "IC604") (pin "20") (pinfunction "ALERT#1_20") (pintype "passive"))
      (node (ref "R611") (pin "2") (pinfunction "2_2") (pintype "passive"))
    )
    (net (code "18") (name "/I2C0_SCL_Zero") (class "Default")
      (node (ref "R620") (pin "1") (pinfunction "1_1") (pintype "passive"))
      (node (ref "R622") (pin "1") (pinfunction "1_1") (pintype "passive"))
    )
    (net (code "19") (name "/I2C0_SDA_Zero") (class "Default")
      (node (ref "R617") (pin "1") (pinfunction "1_1") (pintype "passive"))
      (node (ref "R618") (pin "1") (pinfunction "1_1") (pintype "passive"))
    )
    (net (code "20") (name "/PCIe_CLK_N") (class "Default")
      (node (ref "R604") (pin "1") (pinfunction "1_1") (pintype "passive"))
    )
    (net (code "21") (name "/PCIe_CLK_P") (class "Default")
      (node (ref "R603") (pin "1") (pinfunction "1_1") (pintype "passive"))
    )
    (net (code "22") (name "/PCIe_CLK_nREQ") (class "Default")
      (node (ref "IC602") (pin "30") (pinfunction "PEXCREQ#_30") (pintype "passive"))
    )
    (net (code "23") (name "/PCIe_RX_N") (class "Default")
      (node (ref "C622") (pin "1") (pinfunction "1_1") (pintype "passive"))
    )
    (net (code "24") (name "/PCIe_RX_P") (class "Default")
      (node (ref "C620") (pin "1") (pinfunction "1_1") (pintype "passive"))
    )
    (net (code "25") (name "/PCIe_SPI_CS") (class "Default")
      (node (ref "IC601") (pin "1") (pinfunction "CS_1") (pintype "passive"))
      (node (ref "IC602") (pin "34") (pinfunction "SPICS#_34") (pintype "passive"))
      (node (ref "J601") (pin "7") (pinfunction "CE_7") (pintype "passive"))
    )
    (net (code "26") (name "/PCIe_SPI_SCK") (class "Default")
      (node (ref "IC601") (pin "6") (pinfunction "SCK_6") (pintype "passive"))
      (node (ref "IC602") (pin "35") (pinfunction "SPISCLK_35") (pintype "passive"))
      (node (ref "J601") (pin "4") (pinfunction "CLK_4") (pintype "passive"))
    )
    (net (code "27") (name "/PCIe_SPI_SI") (class "Default")
      (node (ref "IC601") (pin "5") (pinfunction "SI_5") (pintype "passive"))
      (node (ref "IC602") (pin "36") (pinfunction "SPISI_36") (pintype "passive"))
      (node (ref "J601") (pin "2") (pinfunction "MOSI_2") (pintype "passive"))
    )
    (net (code "28") (name "/PCIe_SPI_SO") (class "Default")
      (node (ref "IC601") (pin "2") (pinfunction "SO_2") (pintype "passive"))
      (node (ref "IC602") (pin "33") (pinfunction "SPISO_33") (pintype "passive"))
      (node (ref "J601") (pin "5") (pinfunction "MISO_5") (pintype "passive"))
    )
    (net (code "29") (name "/PCIe_TX_N") (class "Default")
      (node (ref "IC602") (pin "28") (pinfunction "PEXRX0-_28") (pintype "passive"))
    )
    (net (code "30") (name "/PCIe_TX_P") (class "Default")
      (node (ref "IC602") (pin "27") (pinfunction "PEXRX0+_27") (pintype "passive"))
    )
    (net (code "31") (name "/PCIe_WAKE") (class "Default")
      (node (ref "IC602") (pin "20") (pinfunction "PEXWAKE#_20") (pintype "passive"))
      (node (ref "R607") (pin "1") (pinfunction "1_1") (pintype "passive"))
    )
    (net (code "32") (name "/PCIe_XCLK_N") (class "Default")
      (node (ref "IC602") (pin "22") (pinfunction "PEXCLK-_22") (pintype "passive"))
      (node (ref "R604") (pin "2") (pinfunction "2_2") (pintype "passive"))
      (node (ref "R606") (pin "2") (pinfunction "2_2") (pintype "passive"))
    )
    (net (code "33") (name "/PCIe_XCLK_P") (class "Default")
      (node (ref "IC602") (pin "21") (pinfunction "PEXCLK+_21") (pintype "passive"))
      (node (ref "R603") (pin "2") (pinfunction "2_2") (pintype "passive"))
      (node (ref "R605") (pin "2") (pinfunction "2_2") (pintype "passive"))
    )
    (net (code "34") (name "/PCIe_XRX_N") (class "Default")
      (node (ref "C622") (pin "2") (pinfunction "2_2") (pintype "passive"))
      (node (ref "IC602") (pin "25") (pinfunction "PEXTX0-_25") (pintype "passive"))
    )
    (net (code "35") (name "/PCIe_XRX_P") (class "Default")
      (node (ref "C620") (pin "2") (pinfunction "2_2") (pintype "passive"))
      (node (ref "IC602") (pin "24") (pinfunction "PEXTX0+_24") (pintype "passive"))
    )
    (net (code "36") (name "/PCIe_nRST") (class "Default")
      (node (ref "IC602") (pin "19") (pinfunction "PEXRST#_19") (pintype "passive"))
    )
    (net (code "37") (name "/PONRST") (class "Default")
      (node (ref "R608") (pin "2") (pinfunction "2_2") (pintype "passive"))
    )
    (net (code "38") (name "/PRT_CTL3-2") (class "Default")
      (node (ref "IC602") (pin "42") (pinfunction "USBHPE2#_42") (pintype "passive"))
      (node (ref "R615") (pin "2") (pinfunction "2_2") (pintype "passive"))
    )
    (net (code "39") (name "/PRT_CTL3-3") (class "Default")
      (node (ref "IC602") (pin "40") (pinfunction "USBHPE3#_40") (pintype "passive"))
      (node (ref "R621") (pin "2") (pinfunction "2_2") (pintype "passive"))
    )
    (net (code "40") (name "/PRT_CTL3-4") (class "Default")
      (node (ref "IC602") (pin "38") (pinfunction "USBHPE4#_38") (pintype "passive"))
      (node (ref "R616") (pin "2") (pinfunction "2_2") (pintype "passive"))
    )
    (net (code "41") (name "/PWR_EN3-2") (class "Default")
      (node (ref "IC603") (pin "1") (pinfunction "PWR_EN1_1") (pintype "passive"))
      (node (ref "R615") (pin "1") (pinfunction "1_1") (pintype "passive"))
    )
    (net (code "42") (name "/PWR_EN3-3") (class "Default")
      (node (ref "IC603") (pin "15") (pinfunction "PWR_EN2_15") (pintype "passive"))
      (node (ref "R621") (pin "1") (pinfunction "1_1") (pintype "passive"))
    )
    (net (code "43") (name "/PWR_EN3-4") (class "Default")
      (node (ref "IC604") (pin "1") (pinfunction "PWR_EN1_1") (pintype "passive"))
      (node (ref "R616") (pin "1") (pinfunction "1_1") (pintype "passive"))
    )
    (net (code "46") (name "/SPI_HOLD") (class "Default")
      (node (ref "IC601") (pin "7") (pinfunction "HOLD_7") (pintype "passive"))
      (node (ref "J601") (pin "6") (pinfunction "HLD_6") (pintype "passive"))
      (node (ref "R602") (pin "2") (pinfunction "2_2") (pintype "passive"))
    )
    (net (code "47") (name "/SPI_WP") (class "Default")
      (node (ref "IC601") (pin "3") (pinfunction "WP_3") (pintype "passive"))
      (node (ref "J601") (pin "3") (pinfunction "WP_3") (pintype "passive"))
      (node (ref "R601") (pin "2") (pinfunction "2_2") (pintype "passive"))
    )
    (net (code "48") (name "/SSXI") (class "Default")
      (node (ref "C629") (pin "2") (pinfunction "2_2") (pintype "passive"))
      (node (ref "IC602") (pin "47") (pinfunction "SSXI_47") (pintype "passive"))
      (node (ref "X601") (pin "1") (pinfunction "1_1") (pintype "passive"))
    )
    (net (code "49") (name "/SSXO") (class "Default")
      (node (ref "C631") (pin "1") (pinfunction "1_1") (pintype "passive"))
      (node (ref "IC602") (pin "48") (pinfunction "SSXO_48") (pintype "passive"))
      (node (ref "X601") (pin "3") (pinfunction "3_3") (pintype "passive"))
    )
    (net (code "50") (name "/USB2D1_N") (class "Default")
      (node (ref "IC602") (pin "59") (pinfunction "USB2D1-_59") (pintype "passive"))
    )
    (net (code "51") (name "/USB2D1_P") (class "Default")
      (node (ref "IC602") (pin "58") (pinfunction "USB2D1+_58") (pintype "passive"))
    )
    (net (code "52") (name "/USB2D2_N") (class "Default")
      (node (ref "IC602") (pin "68") (pinfunction "USB2D2-_68") (pintype "passive"))
    )
    (net (code "53") (name "/USB2D2_P") (class "Default")
      (node (ref "IC602") (pin "67") (pinfunction "USB2D2+_67") (pintype "passive"))
    )
    (net (code "54") (name "/USB2D3_N") (class "Default")
      (node (ref "IC602") (pin "8") (pinfunction "USB2D3-_8") (pintype "passive"))
    )
    (net (code "55") (name "/USB2D3_P") (class "Default")
      (node (ref "IC602") (pin "7") (pinfunction "USB2D3+_7") (pintype "passive"))
    )
    (net (code "56") (name "/USB2D4_N") (class "Default")
      (node (ref "IC602") (pin "17") (pinfunction "USB2D4-_17") (pintype "passive"))
    )
    (net (code "57") (name "/USB2D4_P") (class "Default")
      (node (ref "IC602") (pin "16") (pinfunction "USB2D4+_16") (pintype "passive"))
    )
    (net (code "58") (name "/USB3-2_5V") (class "Default")
      (node (ref "IC603") (pin "4") (pinfunction "VBUS1_4") (pintype "passive"))
      (node (ref "IC603") (pin "5") (pinfunction "VBUS1_5") (pintype "passive"))
    )
    (net (code "59") (name "/USB3-3_5V") (class "Default")
      (node (ref "IC603") (pin "11") (pinfunction "VBUS2_11") (pintype "passive"))
      (node (ref "IC603") (pin "12") (pinfunction "VBUS2_12") (pintype "passive"))
    )
    (net (code "60") (name "/USB3-4_5V") (class "Default")
      (node (ref "IC604") (pin "4") (pinfunction "VBUS1_4") (pintype "passive"))
      (node (ref "IC604") (pin "5") (pinfunction "VBUS1_5") (pintype "passive"))
    )
    (net (code "61") (name "/USB3RX1_N") (class "Default")
      (node (ref "IC602") (pin "55") (pinfunction "SSRX1+_55") (pintype "passive"))
    )
    (net (code "62") (name "/USB3RX1_P") (class "Default")
      (node (ref "IC602") (pin "56") (pinfunction "SSRX1-_56") (pintype "passive"))
    )
    (net (code "63") (name "/USB3RX2_N") (class "Default")
      (node (ref "IC602") (pin "65") (pinfunction "SSRX2-_65") (pintype "passive"))
    )
    (net (code "64") (name "/USB3RX2_P") (class "Default")
      (node (ref "IC602") (pin "64") (pinfunction "SSRX2+_64") (pintype "passive"))
    )
    (net (code "65") (name "/USB3RX3_N") (class "Default")
      (node (ref "IC602") (pin "5") (pinfunction "SSRX3-_5") (pintype "passive"))
    )
    (net (code "66") (name "/USB3RX3_P") (class "Default")
      (node (ref "IC602") (pin "4") (pinfunction "SSRX3+_4") (pintype "passive"))
    )
    (net (code "67") (name "/USB3RX4_N") (class "Default")
      (node (ref "IC602") (pin "13") (pinfunction "SSRX4+_13") (pintype "passive"))
    )
    (net (code "68") (name "/USB3RX4_P") (class "Default")
      (node (ref "IC602") (pin "14") (pinfunction "SSRX4-_14") (pintype "passive"))
    )
    (net (code "69") (name "/USB3TX1_N") (class "Default")
      (node (ref "C623") (pin "2") (pinfunction "2_2") (pintype "passive"))
    )
    (net (code "70") (name "/USB3TX1_P") (class "Default")
      (node (ref "C621") (pin "2") (pinfunction "2_2") (pintype "passive"))
    )
    (net (code "71") (name "/USB3TX2_N") (class "Default")
      (node (ref "C625") (pin "2") (pinfunction "2_2") (pintype "passive"))
    )
    (net (code "72") (name "/USB3TX2_P") (class "Default")
      (node (ref "C624") (pin "2") (pinfunction "2_2") (pintype "passive"))
    )
    (net (code "73") (name "/USB3TX3_N") (class "Default")
      (node (ref "C627") (pin "2") (pinfunction "2_2") (pintype "passive"))
    )
    (net (code "74") (name "/USB3TX3_P") (class "Default")
      (node (ref "C626") (pin "2") (pinfunction "2_2") (pintype "passive"))
    )
    (net (code "75") (name "/USB3TX4_N") (class "Default")
      (node (ref "C630") (pin "2") (pinfunction "2_2") (pintype "passive"))
    )
    (net (code "76") (name "/USB3TX4_P") (class "Default")
      (node (ref "C628") (pin "2") (pinfunction "2_2") (pintype "passive"))
    )
    (net (code "77") (name "/USB3XTX1_N") (class "Default")
      (node (ref "C623") (pin "1") (pinfunction "1_1") (pintype "passive"))
      (node (ref "IC602") (pin "53") (pinfunction "SSTX1-_53") (pintype "passive"))
    )
    (net (code "78") (name "/USB3XTX1_P") (class "Default")
      (node (ref "C621") (pin "1") (pinfunction "1_1") (pintype "passive"))
      (node (ref "IC602") (pin "52") (pinfunction "SSTX1+_52") (pintype "passive"))
    )
    (net (code "79") (name "/USB3XTX2_N") (class "Default")
      (node (ref "C625") (pin "1") (pinfunction "1_1") (pintype "passive"))
      (node (ref "IC602") (pin "62") (pinfunction "SSTX2-_62") (pintype "passive"))
    )
    (net (code "80") (name "/USB3XTX2_P") (class "Default")
      (node (ref "C624") (pin "1") (pinfunction "1_1") (pintype "passive"))
      (node (ref "IC602") (pin "61") (pinfunction "SSTX2+_61") (pintype "passive"))
    )
    (net (code "81") (name "/USB3XTX3_N") (class "Default")
      (node (ref "C627") (pin "1") (pinfunction "1_1") (pintype "passive"))
      (node (ref "IC602") (pin "2") (pinfunction "SSTX3-_2") (pintype "passive"))
    )
    (net (code "82") (name "/USB3XTX3_P") (class "Default")
      (node (ref "C626") (pin "1") (pinfunction "1_1") (pintype "passive"))
      (node (ref "IC602") (pin "1") (pinfunction "SSTX3+_1") (pintype "passive"))
    )
    (net (code "83") (name "/USB3XTX4_N") (class "Default")
      (node (ref "C630") (pin "1") (pinfunction "1_1") (pintype "passive"))
      (node (ref "IC602") (pin "11") (pinfunction "SSTX4-_11") (pintype "passive"))
    )
    (net (code "84") (name "/USB3XTX4_P") (class "Default")
      (node (ref "C628") (pin "1") (pinfunction "1_1") (pintype "passive"))
      (node (ref "IC602") (pin "10") (pinfunction "SSTX4+_10") (pintype "passive"))
    )
    (net (code "92") (name "GND") (class "Default")
      (node (ref "C601") (pin "2") (pinfunction "2_2") (pintype "passive"))
      (node (ref "C602") (pin "2") (pinfunction "2_2") (pintype "passive"))
      (node (ref "C603") (pin "2") (pinfunction "2_2") (pintype "passive"))
      (node (ref "C604") (pin "2") (pinfunction "2_2") (pintype "passive"))
      (node (ref "C605") (pin "2") (pinfunction "2_2") (pintype "passive"))
      (node (ref "C606") (pin "2") (pinfunction "2_2") (pintype "passive"))
      (node (ref "C607") (pin "2") (pinfunction "2_2") (pintype "passive"))
      (node (ref "C608") (pin "2") (pinfunction "2_2") (pintype "passive"))
      (node (ref "C609") (pin "2") (pinfunction "2_2") (pintype "passive"))
      (node (ref "C610") (pin "2") (pinfunction "2_2") (pintype "passive"))
      (node (ref "C611") (pin "2") (pinfunction "2_2") (pintype "passive"))
      (node (ref "C612") (pin "2") (pinfunction "2_2") (pintype "passive"))
      (node (ref "C613") (pin "2") (pinfunction "2_2") (pintype "passive"))
      (node (ref "C614") (pin "2") (pinfunction "2_2") (pintype "passive"))
      (node (ref "C615") (pin "2") (pinfunction "2_2") (pintype "passive"))
      (node (ref "C616") (pin "2") (pinfunction "2_2") (pintype "passive"))
      (node (ref "C617") (pin "2") (pinfunction "2_2") (pintype "passive"))
      (node (ref "C618") (pin "2") (pinfunction "2_2") (pintype "passive"))
      (node (ref "C619") (pin "2") (pinfunction "2_2") (pintype "passive"))
      (node (ref "C629") (pin "1") (pinfunction "1_1") (pintype "passive"))
      (node (ref "C631") (pin "2") (pinfunction "2_2") (pintype "passive"))
      (node (ref "C632") (pin "2") (pinfunction "2_2") (pintype "passive"))
      (node (ref "C633") (pin "2") (pinfunction "2_2") (pintype "passive"))
      (node (ref "C634") (pin "2") (pinfunction "2_2") (pintype "passive"))
      (node (ref "C635") (pin "2") (pinfunction "2_2") (pintype "passive"))
      (node (ref "C636") (pin "2") (pinfunction "2_2") (pintype "passive"))
      (node (ref "C637") (pin "2") (pinfunction "2_2") (pintype "passive"))
      (node (ref "C638") (pin "2") (pinfunction "2_2") (pintype "passive"))
      (node (ref "C639") (pin "2") (pinfunction "2_2") (pintype "passive"))
      (node (ref "C640") (pin "2") (pinfunction "2_2") (pintype "passive"))
      (node (ref "C641") (pin "2") (pinfunction "2_2") (pintype "passive"))
      (node (ref "IC601") (pin "4") (pinfunction "GND_4") (pintype "passive"))
      (node (ref "IC602") (pin "69") (pinfunction "GND_69") (pintype "passive"))
      (node (ref "IC603") (pin "14") (pinfunction "GND_14") (pintype "passive"))
      (node (ref "IC603") (pin "17") (pinfunction "GND_17") (pintype "passive"))
      (node (ref "IC603") (pin "2") (pinfunction "GND_2") (pintype "passive"))
      (node (ref "IC604") (pin "14") (pinfunction "GND_14") (pintype "passive"))
      (node (ref "IC604") (pin "17") (pinfunction "GND_17") (pintype "passive"))
      (node (ref "IC604") (pin "2") (pinfunction "GND_2") (pintype "passive"))
      (node (ref "J601") (pin "1") (pinfunction "GND_1") (pintype "passive"))
      (node (ref "R605") (pin "1") (pinfunction "1_1") (pintype "passive"))
      (node (ref "R606") (pin "1") (pinfunction "1_1") (pintype "passive"))
      (node (ref "R610") (pin "1") (pinfunction "1_1") (pintype "passive"))
      (node (ref "R619") (pin "1") (pinfunction "1_1") (pintype "passive"))
      (node (ref "X601") (pin "2") (pinfunction "2_2") (pintype "passive"))
      (node (ref "X601") (pin "4") (pinfunction "4_4") (pintype "passive"))
    )
    (net (code "93") (name "Net-(IC602-PONRST#)") (class "Default")
      (node (ref "IC602") (pin "31") (pinfunction "PONRST#_31") (pintype "passive"))
      (node (ref "R608") (pin "1") (pinfunction "1_1") (pintype "passive"))
      (node (ref "R619") (pin "2") (pinfunction "2_2") (pintype "passive"))
    )
    (net (code "94") (name "Net-(IC602-SMI#)") (class "Default")
      (node (ref "IC602") (pin "18") (pinfunction "SMI#_18") (pintype "passive"))
      (node (ref "R609") (pin "2") (pinfunction "2_2") (pintype "passive"))
    )
    (net (code "95") (name "Net-(IC602-SSREXT)") (class "Default")
      (node (ref "IC602") (pin "50") (pinfunction "SSREXT_50") (pintype "passive"))
      (node (ref "R610") (pin "2") (pinfunction "2_2") (pintype "passive"))
    )
    (net (code "96") (name "Net-(IC602-USBHOC1#)") (class "Default")
      (node (ref "IC602") (pin "43") (pinfunction "USBHOC1#_43") (pintype "passive"))
      (node (ref "R614") (pin "2") (pinfunction "2_2") (pintype "passive"))
    )
    (net (code "97") (name "Net-(IC603-BOOST#)") (class "Default")
      (node (ref "IC603") (pin "13") (pinfunction "BOOST#_13") (pintype "passive"))
      (node (ref "R623") (pin "1") (pinfunction "1_1") (pintype "passive"))
    )
    (net (code "98") (name "Net-(IC603-COMM_ILIM)") (class "Default")
      (node (ref "IC603") (pin "3") (pinfunction "COMM_ILIM_3") (pintype "passive"))
      (node (ref "R625") (pin "2") (pinfunction "2_2") (pintype "passive"))
    )
    (net (code "99") (name "Net-(IC603-SMCLK)") (class "Default")
      (node (ref "IC603") (pin "19") (pinfunction "SMCLK_19") (pintype "passive"))
      (node (ref "R620") (pin "2") (pinfunction "2_2") (pintype "passive"))
    )
    (net (code "100") (name "Net-(IC603-SMDATA)") (class "Default")
      (node (ref "IC603") (pin "18") (pinfunction "SMDATA_18") (pintype "passive"))
      (node (ref "R617") (pin "2") (pinfunction "2_2") (pintype "passive"))
    )
    (net (code "101") (name "Net-(IC604-BOOST#)") (class "Default")
      (node (ref "IC604") (pin "13") (pinfunction "BOOST#_13") (pintype "passive"))
      (node (ref "R624") (pin "1") (pinfunction "1_1") (pintype "passive"))
    )
    (net (code "102") (name "Net-(IC604-COMM_ILIM)") (class "Default")
      (node (ref "IC604") (pin "3") (pinfunction "COMM_ILIM_3") (pintype "passive"))
      (node (ref "R626") (pin "2") (pinfunction "2_2") (pintype "passive"))
    )
    (net (code "103") (name "Net-(IC604-SMCLK)") (class "Default")
      (node (ref "IC604") (pin "19") (pinfunction "SMCLK_19") (pintype "passive"))
      (node (ref "R622") (pin "2") (pinfunction "2_2") (pintype "passive"))
    )
    (net (code "104") (name "Net-(IC604-SMDATA)") (class "Default")
      (node (ref "IC604") (pin "18") (pinfunction "SMDATA_18") (pintype "passive"))
      (node (ref "R618") (pin "2") (pinfunction "2_2") (pintype "passive"))
    )
    (net (code "105") (name "unconnected-(IC602-RESERVED-Pad26)") (class "Default")
      (node (ref "IC602") (pin "26") (pinfunction "RESERVED_26") (pintype "passive+no_connect"))
    )
    (net (code "106") (name "unconnected-(IC602-TESTEN{slash}NC-Pad51)") (class "Default")
      (node (ref "IC602") (pin "51") (pinfunction "TESTEN/NC_51") (pintype "passive+no_connect"))
    )
    (net (code "107") (name "unconnected-(IC602-USBHPE1#-Pad44)") (class "Default")
      (node (ref "IC602") (pin "44") (pinfunction "USBHPE1#_44") (pintype "passive"))
    )
    (net (code "108") (name "unconnected-(IC604-ALERT#2-Pad16)") (class "Default")
      (node (ref "IC604") (pin "16") (pinfunction "ALERT#2_16") (pintype "passive"))
    )
    (net (code "109") (name "unconnected-(IC604-VBUS2-Pad11)") (class "Default")
      (node (ref "IC604") (pin "11") (pinfunction "VBUS2_11") (pintype "passive"))
    )
    (net (code "110") (name "unconnected-(IC604-VBUS2-Pad12)") (class "Default")
      (node (ref "IC604") (pin "12") (pinfunction "VBUS2_12") (pintype "passive"))
    )
  )
)
